# MB.net
KiCad netlist of a schematic drawn in Altium Designer
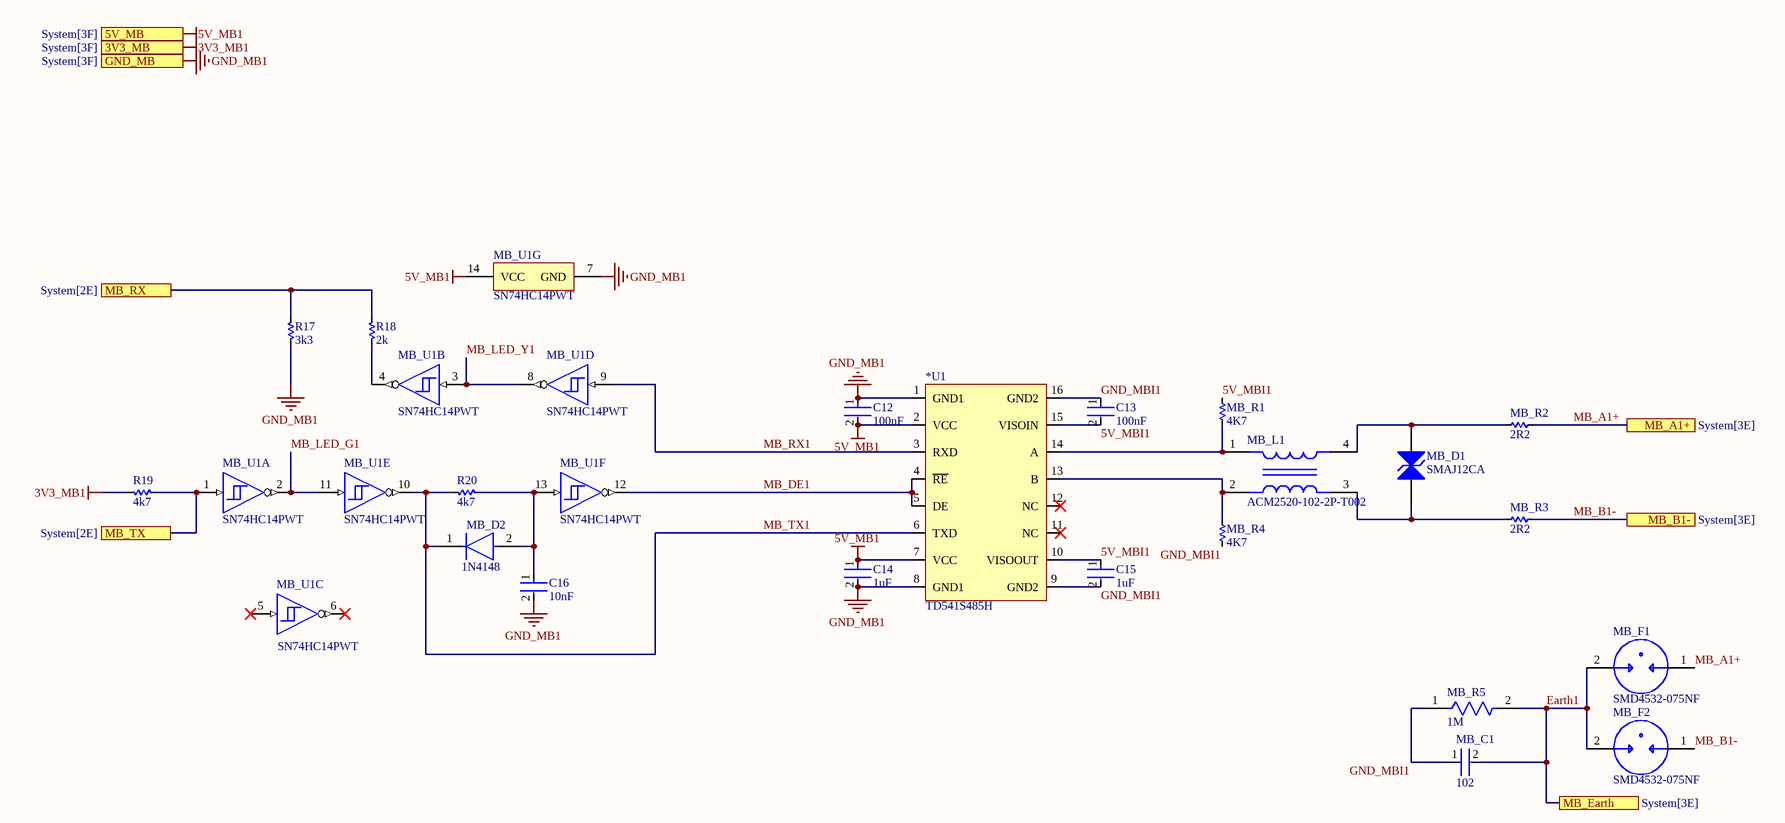
[diagram p0: MB.SchDoc]

(export (version "E")
  (design (tool "Eeschema 10.0.6"))
  (components
    (comp (ref "*U1")
      (value "TD541S485H")
      (footprint "TD(H)541S485H")
      (description "TD541S485H IC Transceiver RS-485/RS-422 DFN-16")
      (libsource (lib "atlab_altium_lib") (part "TD(H)541S485H"))
    )
    (comp (ref "C12")
      (value "100nF")
      (footprint "FP-GRM21B-0_15-MFG")
      (description "Cap 0805 10%")
      (fields (field (name "VOLTAGE") "6.3V") (field (name "TOLERANCE") "20%"))
      (libsource (lib "Altium Content Vault") (part "b4654b650e69147ec39a6b967a45e02"))
    )
    (comp (ref "C13")
      (value "100nF")
      (footprint "FP-GRM21B-0_15-MFG")
      (description "Cap 0805 10%")
      (fields (field (name "VOLTAGE") "6.3V") (field (name "TOLERANCE") "20%"))
      (libsource (lib "Altium Content Vault") (part "b4654b650e69147ec39a6b967a45e02"))
    )
    (comp (ref "C14")
      (value "1uF")
      (footprint "FP-GRM21B-0_15-MFG")
      (description "Cap 0805 10%")
      (fields (field (name "VOLTAGE") "6.3V") (field (name "TOLERANCE") "20%"))
      (libsource (lib "Altium Content Vault") (part "b4654b650e69147ec39a6b967a45e02"))
    )
    (comp (ref "C15")
      (value "1uF")
      (footprint "FP-GRM21B-0_15-MFG")
      (description "Cap 0805 10%")
      (fields (field (name "VOLTAGE") "6.3V") (field (name "TOLERANCE") "20%"))
      (libsource (lib "Altium Content Vault") (part "b4654b650e69147ec39a6b967a45e02"))
    )
    (comp (ref "C16")
      (value "10nF")
      (footprint "FP-GRM21B-0_15-MFG")
      (description "Cap 0805 10%")
      (fields (field (name "VOLTAGE") "6.3V") (field (name "TOLERANCE") "20%"))
      (libsource (lib "Altium Content Vault") (part "b4654b650e69147ec39a6b967a45e02"))
    )
    (comp (ref "MB_C1")
      (value "102")
      (footprint "FP-GRM32-0_3-MFG")
      (description "Tụ 1nF 1210 2000V 10%")
      (fields
        (field (name "OCTOPART") "https://octopart.com/grm32er60j107me20l-murata-197007")
        (field (name "3DS PART NUMBER") "220-00002")
      )
      (libsource (lib "Altium Content Vault") (part "11868f565c42a9108669ba33697ecf6"))
    )
    (comp (ref "MB_D1")
      (value "SMAJ12CA")
      (footprint "VISH-DO-214AC-2_N")
      (description "SMAJ12CA TVS DIODE 12VWM 19.9VC DO214AC")
      (fields
        (field (name "MANUFACTURER") "Vishay Semiconductor")
        (field (name "PARTNUMBER") "SMAJ8.5CA-E3/61")
      )
      (libsource (lib "Altium Content Vault") (part "VISH-A1A2-2"))
    )
    (comp (ref "MB_D2")
      (value "1N4148")
      (footprint "FP-DO-213AA-MFG")
      (description "1N4148 LL4148 SOD-80/1206 SMD")
      (fields
        (field (name "OCTOPART") "https://octopart.com/jantx1n4148ur-1-microsemi-6804654")
        (field (name "MANUFACTURER PART NUMBER") "JANTX1N4148UR-1")
      )
      (libsource (lib "Altium Content Vault") (part "d7152d700b627762746794eb795d46e"))
    )
    (comp (ref "MB_F1")
      (value "SMD4532-075NF")
      (footprint "FP-SG-MFG")
      (libsource (lib "Altium Content Vault") (part "8ad3d6bd83fc463b22fef6295d9c762"))
    )
    (comp (ref "MB_F2")
      (value "SMD4532-075NF")
      (footprint "FP-SG-MFG")
      (libsource (lib "Altium Content Vault") (part "8ad3d6bd83fc463b22fef6295d9c762"))
    )
    (comp (ref "MB_L1")
      (value "ACM2520-102-2P-T002")
      (footprint "FP-ACM2520-2P-MFG")
      (description "ACM2520-102-2P-T002 CMC 200MA 2LN 1KOHM SMD")
      (libsource (lib "Altium Content Vault") (part "d0b2d54a63b95a1e21836838efe74ed"))
    )
    (comp (ref "MB_R1")
      (value "4K7")
      (footprint "RES-SMD-0805")
      (description "Res 0805 5%")
      (fields
        (field (name "MANUFACTURER") "Generic Components")
        (field (name "PUBLISHER") "Altium Hobart Technology Centre")
      )
      (libsource (lib "TechMT.VN_Lib_Project v2") (part "Res-SMD"))
    )
    (comp (ref "MB_R2")
      (value "2R2")
      (footprint "RES-SMD-0805")
      (description "Res 0805 5%")
      (fields
        (field (name "MANUFACTURER") "Generic Components")
        (field (name "PUBLISHER") "Altium Hobart Technology Centre")
      )
      (libsource (lib "TechMT.VN_Lib_Project v2") (part "Res-SMD"))
    )
    (comp (ref "MB_R3")
      (value "2R2")
      (footprint "RES-SMD-0805")
      (description "Res 0805 5%")
      (fields
        (field (name "MANUFACTURER") "Generic Components")
        (field (name "PUBLISHER") "Altium Hobart Technology Centre")
      )
      (libsource (lib "TechMT.VN_Lib_Project v2") (part "Res-SMD"))
    )
    (comp (ref "MB_R4")
      (value "4K7")
      (footprint "RES-SMD-0805")
      (description "Res 0805 5%")
      (fields
        (field (name "MANUFACTURER") "Generic Components")
        (field (name "PUBLISHER") "Altium Hobart Technology Centre")
      )
      (libsource (lib "TechMT.VN_Lib_Project v2") (part "Res-SMD"))
    )
    (comp (ref "MB_R5")
      (value "1M")
      (footprint "FP-RC1206-MFG")
      (description "RES SMD 1/4W 1206")
      (fields
        (field (name "MANUFACTURER PART NUMBER") "RC1206JR-070RL")
        (field (name "MANUFACTURER") "YAGEO")
      )
      (libsource (lib "Altium Content Vault") (part "1029c3af85768c4190bb7ad29bc67b5"))
    )
    (comp (ref "MB_U1")
      (value "SN74HC14PWT")
      (footprint "PW0014A_M")
      (description "Hex Schmitt-Trigger Inverters, PW0014A, SMALL T&R")
      (fields
        (field (name "GENERIC PART NUMBER") "SN74HC14")
        (field (name "MANUFACTURER") "Texas Instruments")
      )
      (libsource (lib "Altium Content Vault") (part "TI-CD_SNX4XXXXXX4X_19A-14-SCHMITT"))
    )
    (comp (ref "R17")
      (value "3k3")
      (footprint "RES-SMD-0603")
      (description "Res 0603 5%")
      (fields
        (field (name "MANUFACTURER") "Generic Components")
        (field (name "PUBLISHER") "Altium Hobart Technology Centre")
      )
      (libsource (lib "TechMT.VN_Lib_Project v2") (part "Res-SMD"))
    )
    (comp (ref "R18")
      (value "2k")
      (footprint "RES-SMD-0603")
      (description "Res 0603 5%")
      (fields
        (field (name "MANUFACTURER") "Generic Components")
        (field (name "PUBLISHER") "Altium Hobart Technology Centre")
      )
      (libsource (lib "TechMT.VN_Lib_Project v2") (part "Res-SMD"))
    )
    (comp (ref "R19")
      (value "4k7")
      (footprint "RES-SMD-0603")
      (description "Res 0603 5%")
      (fields
        (field (name "MANUFACTURER") "Generic Components")
        (field (name "PUBLISHER") "Altium Hobart Technology Centre")
      )
      (libsource (lib "TechMT.VN_Lib_Project v2") (part "Res-SMD"))
    )
    (comp (ref "R20")
      (value "4k7")
      (footprint "RES-SMD-0603")
      (description "Res 0603 5%")
      (fields
        (field (name "MANUFACTURER") "Generic Components")
        (field (name "PUBLISHER") "Altium Hobart Technology Centre")
      )
      (libsource (lib "TechMT.VN_Lib_Project v2") (part "Res-SMD"))
    )
  )
  (nets
    (net (code "1") (name "/5V_MBI1") (class "Default")
      (node (ref "*U1") (pin "10") (pinfunction "VISOOUT_10") (pintype "passive"))
      (node (ref "*U1") (pin "15") (pinfunction "VISOIN_15") (pintype "passive"))
      (node (ref "C13") (pin "2") (pinfunction "2_2") (pintype "passive"))
      (node (ref "C15") (pin "1") (pinfunction "1_1") (pintype "passive"))
      (node (ref "MB_R1") (pin "2") (pinfunction "2_2") (pintype "passive"))
    )
    (net (code "2") (name "/Earth1") (class "Default")
      (node (ref "MB_C1") (pin "2") (pinfunction "2_2") (pintype "passive"))
      (node (ref "MB_F1") (pin "2") (pinfunction "2_2") (pintype "passive"))
      (node (ref "MB_F2") (pin "2") (pinfunction "2_2") (pintype "passive"))
      (node (ref "MB_R5") (pin "2") (pinfunction "2_2") (pintype "passive"))
    )
    (net (code "3") (name "/GND_MBI1") (class "Default")
      (node (ref "*U1") (pin "16") (pinfunction "GND2_16") (pintype "passive"))
      (node (ref "*U1") (pin "9") (pinfunction "GND2_9") (pintype "passive"))
      (node (ref "C13") (pin "1") (pinfunction "1_1") (pintype "passive"))
      (node (ref "C15") (pin "2") (pinfunction "2_2") (pintype "passive"))
      (node (ref "MB_C1") (pin "1") (pinfunction "1_1") (pintype "passive"))
      (node (ref "MB_R4") (pin "1") (pinfunction "1_1") (pintype "passive"))
      (node (ref "MB_R5") (pin "1") (pinfunction "1_1") (pintype "passive"))
    )
    (net (code "4") (name "/MB_A1+") (class "Default")
      (node (ref "MB_F1") (pin "1") (pinfunction "1_1") (pintype "passive"))
      (node (ref "MB_R2") (pin "1") (pinfunction "1_1") (pintype "passive"))
    )
    (net (code "5") (name "/MB_B1-") (class "Default")
      (node (ref "MB_F2") (pin "1") (pinfunction "1_1") (pintype "passive"))
      (node (ref "MB_R3") (pin "1") (pinfunction "1_1") (pintype "passive"))
    )
    (net (code "6") (name "/MB_DE1") (class "Default")
      (node (ref "*U1") (pin "4") (pinfunction "~{RE}_4") (pintype "passive"))
      (node (ref "*U1") (pin "5") (pinfunction "DE_5") (pintype "passive"))
      (node (ref "MB_U1") (pin "12") (pinfunction "~{6Y}_12") (pintype "output"))
    )
    (net (code "7") (name "/MB_LED_G1") (class "Default")
      (node (ref "MB_U1") (pin "11") (pinfunction "5A_11") (pintype "input"))
      (node (ref "MB_U1") (pin "2") (pinfunction "~{1Y}_2") (pintype "output"))
    )
    (net (code "8") (name "/MB_LED_Y1") (class "Default")
      (node (ref "MB_U1") (pin "3") (pinfunction "2A_3") (pintype "input"))
      (node (ref "MB_U1") (pin "8") (pinfunction "~{4Y}_8") (pintype "output"))
    )
    (net (code "9") (name "/MB_RX") (class "Default")
      (node (ref "R17") (pin "2") (pinfunction "2_2") (pintype "passive"))
      (node (ref "R18") (pin "2") (pinfunction "2_2") (pintype "passive"))
    )
    (net (code "10") (name "/MB_RX1") (class "Default")
      (node (ref "*U1") (pin "3") (pinfunction "RXD_3") (pintype "passive"))
      (node (ref "MB_U1") (pin "9") (pinfunction "4A_9") (pintype "input"))
    )
    (net (code "11") (name "/MB_TX") (class "Default")
      (node (ref "MB_U1") (pin "1") (pinfunction "1A_1") (pintype "input"))
      (node (ref "R19") (pin "1") (pinfunction "1_1") (pintype "passive"))
    )
    (net (code "12") (name "/MB_TX1") (class "Default")
      (node (ref "*U1") (pin "6") (pinfunction "TXD_6") (pintype "passive"))
      (node (ref "MB_D2") (pin "1") (pinfunction "C_1") (pintype "passive"))
      (node (ref "MB_U1") (pin "10") (pinfunction "~{5Y}_10") (pintype "output"))
      (node (ref "R20") (pin "2") (pinfunction "2_2") (pintype "passive"))
    )
    (net (code "13") (name "3V3_MB1") (class "Default")
      (node (ref "R19") (pin "2") (pinfunction "2_2") (pintype "passive"))
    )
    (net (code "14") (name "5V_MB1") (class "Default")
      (node (ref "*U1") (pin "2") (pinfunction "VCC_2") (pintype "passive"))
      (node (ref "*U1") (pin "7") (pinfunction "VCC_7") (pintype "passive"))
      (node (ref "C12") (pin "2") (pinfunction "2_2") (pintype "passive"))
      (node (ref "C14") (pin "1") (pinfunction "1_1") (pintype "passive"))
      (node (ref "MB_U1") (pin "14") (pinfunction "VCC_14") (pintype "power_in"))
    )
    (net (code "15") (name "GND_MB1") (class "Default")
      (node (ref "*U1") (pin "1") (pinfunction "GND1_1") (pintype "passive"))
      (node (ref "*U1") (pin "8") (pinfunction "GND1_8") (pintype "passive"))
      (node (ref "C12") (pin "1") (pinfunction "1_1") (pintype "passive"))
      (node (ref "C14") (pin "2") (pinfunction "2_2") (pintype "passive"))
      (node (ref "C16") (pin "2") (pinfunction "2_2") (pintype "passive"))
      (node (ref "MB_U1") (pin "7") (pinfunction "GND_7") (pintype "power_in"))
      (node (ref "R17") (pin "1") (pinfunction "1_1") (pintype "passive"))
    )
    (net (code "16") (name "Net-(*U1-A)") (class "Default")
      (node (ref "*U1") (pin "14") (pinfunction "A_14") (pintype "passive"))
      (node (ref "MB_L1") (pin "1") (pinfunction "1_1") (pintype "passive"))
      (node (ref "MB_R1") (pin "1") (pinfunction "1_1") (pintype "passive"))
    )
    (net (code "17") (name "Net-(*U1-B)") (class "Default")
      (node (ref "*U1") (pin "13") (pinfunction "B_13") (pintype "passive"))
      (node (ref "MB_L1") (pin "2") (pinfunction "2_2") (pintype "passive"))
      (node (ref "MB_R4") (pin "2") (pinfunction "2_2") (pintype "passive"))
    )
    (net (code "18") (name "Net-(MB_D1-A1)") (class "Default")
      (node (ref "MB_D1") (pin "1") (pinfunction "A1_1") (pintype "passive"))
      (node (ref "MB_L1") (pin "3") (pinfunction "3_3") (pintype "passive"))
      (node (ref "MB_R3") (pin "2") (pinfunction "2_2") (pintype "passive"))
    )
    (net (code "19") (name "Net-(MB_D1-A2)") (class "Default")
      (node (ref "MB_D1") (pin "2") (pinfunction "A2_2") (pintype "passive"))
      (node (ref "MB_L1") (pin "4") (pinfunction "4_4") (pintype "passive"))
      (node (ref "MB_R2") (pin "2") (pinfunction "2_2") (pintype "passive"))
    )
    (net (code "20") (name "Net-(MB_D2-A)") (class "Default")
      (node (ref "C16") (pin "1") (pinfunction "1_1") (pintype "passive"))
      (node (ref "MB_D2") (pin "2") (pinfunction "A_2") (pintype "passive"))
      (node (ref "MB_U1") (pin "13") (pinfunction "6A_13") (pintype "input"))
      (node (ref "R20") (pin "1") (pinfunction "1_1") (pintype "passive"))
    )
    (net (code "21") (name "Net-(MB_U1B-~{2Y})") (class "Default")
      (node (ref "MB_U1") (pin "4") (pinfunction "~{2Y}_4") (pintype "output"))
      (node (ref "R18") (pin "1") (pinfunction "1_1") (pintype "passive"))
    )
    (net (code "22") (name "unconnected-(*U1-NC-Pad11)") (class "Default")
      (node (ref "*U1") (pin "11") (pinfunction "NC_11") (pintype "passive+no_connect"))
    )
    (net (code "23") (name "unconnected-(*U1-NC-Pad12)") (class "Default")
      (node (ref "*U1") (pin "12") (pinfunction "NC_12") (pintype "passive+no_connect"))
    )
    (net (code "24") (name "unconnected-(MB_U1C-3A-Pad5)") (class "Default")
      (node (ref "MB_U1") (pin "5") (pinfunction "3A_5") (pintype "input+no_connect"))
    )
    (net (code "25") (name "unconnected-(MB_U1C-~{3Y}-Pad6)") (class "Default")
      (node (ref "MB_U1") (pin "6") (pinfunction "~{3Y}_6") (pintype "output+no_connect"))
    )
  )
)
